# audio.net
KiCad netlist of a schematic drawn in EAGLE
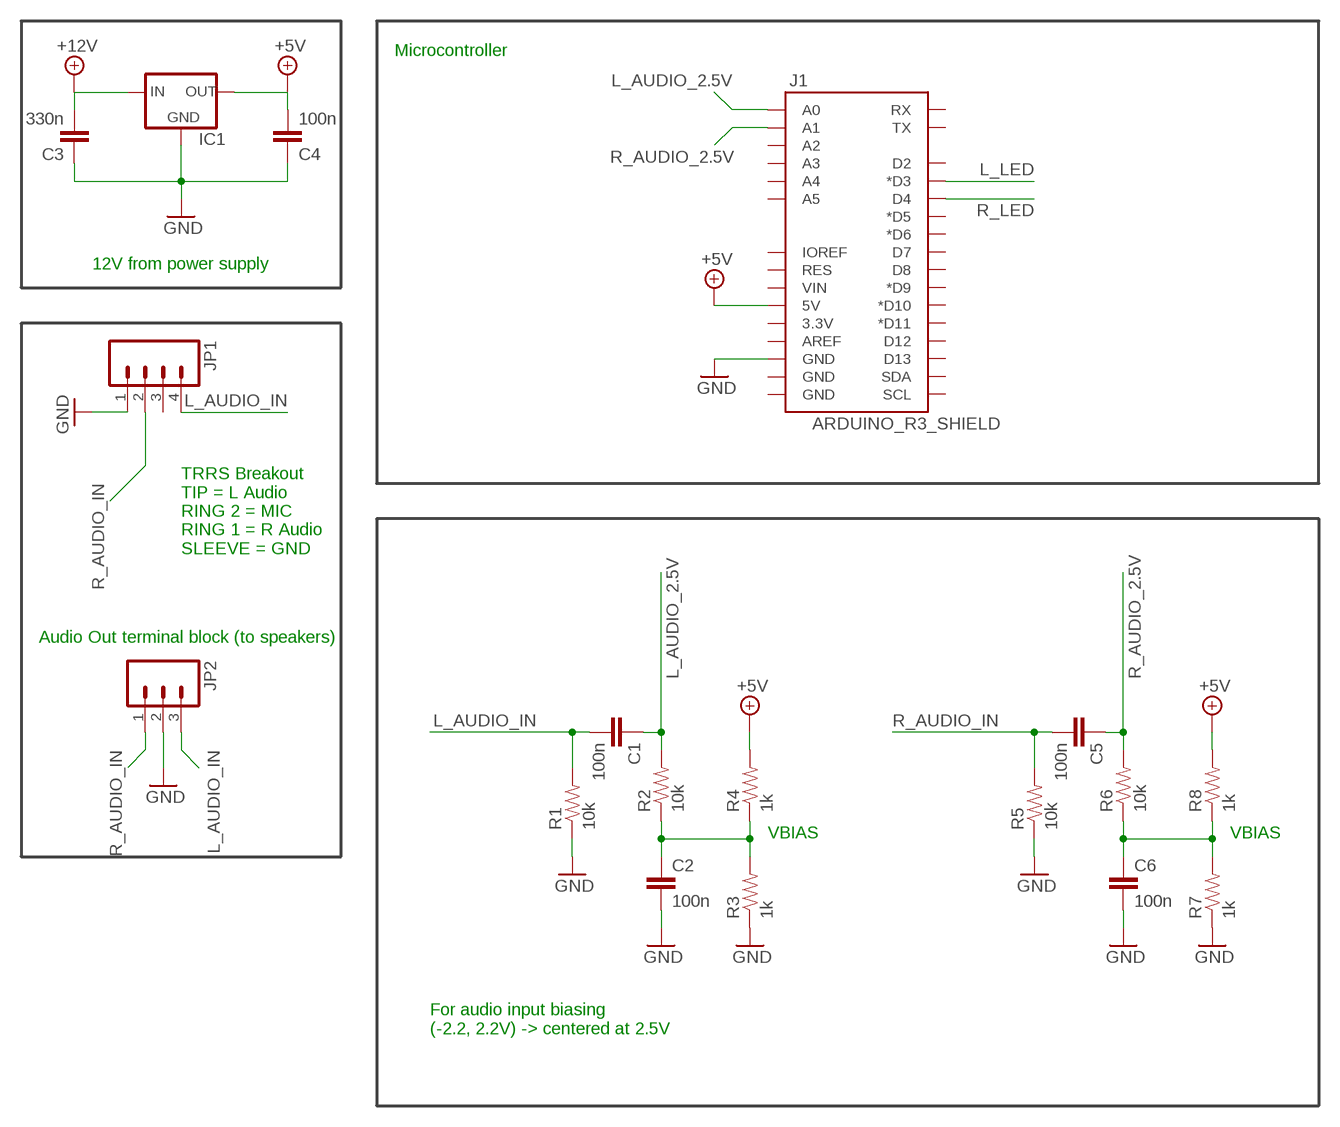
[diagram p0: schematic, sheet 1]

(export (version "E")
  (design (tool "Eeschema 10.0.6"))
  (components
    (comp (ref "C1")
      (value "100n")
      (footprint "eagle-import:AXIAL-5MM")
      (libsource (lib "eagle-import") (part "CAP_"))
    )
    (comp (ref "C2")
      (value "100n")
      (footprint "eagle-import:AXIAL-5MM")
      (libsource (lib "eagle-import") (part "CAP_"))
    )
    (comp (ref "C3")
      (value "330n")
      (footprint "eagle-import:AXIAL-5MM")
      (libsource (lib "eagle-import") (part "CAP_"))
    )
    (comp (ref "C4")
      (value "100n")
      (footprint "eagle-import:AXIAL-5MM")
      (libsource (lib "eagle-import") (part "CAP_"))
    )
    (comp (ref "C5")
      (value "100n")
      (footprint "eagle-import:AXIAL-5MM")
      (libsource (lib "eagle-import") (part "CAP_"))
    )
    (comp (ref "C6")
      (value "100n")
      (footprint "eagle-import:AXIAL-5MM")
      (libsource (lib "eagle-import") (part "CAP_"))
    )
    (comp (ref "IC1")
      (value "5VREG_L7805SPACED")
      (footprint "eagle-import:TO-220-SPACED")
      (libsource (lib "eagle-import") (part "5VREG_L7805SPACED"))
    )
    (comp (ref "J1")
      (value "ARDUINO_R3_SHIELD")
      (footprint "eagle-import:UNO_R3_SHIELD")
      (libsource (lib "eagle-import") (part "ARDUINO_R3_SHIELD"))
    )
    (comp (ref "JP1")
      (value "M04")
      (footprint "eagle-import:1X04")
      (libsource (lib "eagle-import") (part "M04"))
    )
    (comp (ref "JP2")
      (value "M03")
      (footprint "eagle-import:1X03")
      (libsource (lib "eagle-import") (part "M03"))
    )
    (comp (ref "R1")
      (value "10k")
      (footprint "eagle-import:AXIAL-0.4")
      (libsource (lib "eagle-import") (part "RESISTORPTH-1/4W"))
    )
    (comp (ref "R2")
      (value "10k")
      (footprint "eagle-import:AXIAL-0.4")
      (libsource (lib "eagle-import") (part "RESISTORPTH-1/4W"))
    )
    (comp (ref "R3")
      (value "1k")
      (footprint "eagle-import:AXIAL-0.4")
      (libsource (lib "eagle-import") (part "RESISTORPTH-1/4W"))
    )
    (comp (ref "R4")
      (value "1k")
      (footprint "eagle-import:AXIAL-0.4")
      (libsource (lib "eagle-import") (part "RESISTORPTH-1/4W"))
    )
    (comp (ref "R5")
      (value "10k")
      (footprint "eagle-import:AXIAL-0.4")
      (libsource (lib "eagle-import") (part "RESISTORPTH-1/4W"))
    )
    (comp (ref "R6")
      (value "10k")
      (footprint "eagle-import:AXIAL-0.4")
      (libsource (lib "eagle-import") (part "RESISTORPTH-1/4W"))
    )
    (comp (ref "R7")
      (value "1k")
      (footprint "eagle-import:AXIAL-0.4")
      (libsource (lib "eagle-import") (part "RESISTORPTH-1/4W"))
    )
    (comp (ref "R8")
      (value "1k")
      (footprint "eagle-import:AXIAL-0.4")
      (libsource (lib "eagle-import") (part "RESISTORPTH-1/4W"))
    )
  )
  (nets
    (net (code "1") (name "+5V") (class "Default")
      (node (ref "C4") (pin "P$2") (pinfunction "2_P$2") (pintype "passive"))
      (node (ref "IC1") (pin "3") (pinfunction "OUT_3") (pintype "output"))
      (node (ref "J1") (pin "5V") (pinfunction "5V_5V") (pintype "bidirectional"))
      (node (ref "R4") (pin "P$2") (pinfunction "2_P$2") (pintype "passive"))
      (node (ref "R8") (pin "P$2") (pinfunction "2_P$2") (pintype "passive"))
    )
    (net (code "2") (name "+12V") (class "Default")
      (node (ref "C3") (pin "P$2") (pinfunction "2_P$2") (pintype "passive"))
      (node (ref "IC1") (pin "1") (pinfunction "IN_1") (pintype "input"))
    )
    (net (code "3") (name "/L_AUDIO_2.5V") (class "Default")
      (node (ref "C1") (pin "P$1") (pinfunction "1_P$1") (pintype "passive"))
      (node (ref "J1") (pin "A0") (pinfunction "A0_A0") (pintype "bidirectional"))
      (node (ref "R2") (pin "P$2") (pinfunction "2_P$2") (pintype "passive"))
    )
    (net (code "4") (name "/L_AUDIO_IN") (class "Default")
      (node (ref "C1") (pin "P$2") (pinfunction "2_P$2") (pintype "passive"))
      (node (ref "JP1") (pin "4") (pinfunction "4_4") (pintype "passive"))
      (node (ref "JP2") (pin "3") (pinfunction "3_3") (pintype "passive"))
      (node (ref "R1") (pin "P$2") (pinfunction "2_P$2") (pintype "passive"))
    )
    (net (code "5") (name "/L_LED") (class "Default")
      (node (ref "J1") (pin "D3") (pinfunction "*D3_D3") (pintype "bidirectional"))
    )
    (net (code "6") (name "/R_AUDIO_2.5V") (class "Default")
      (node (ref "C5") (pin "P$1") (pinfunction "1_P$1") (pintype "passive"))
      (node (ref "J1") (pin "A1") (pinfunction "A1_A1") (pintype "bidirectional"))
      (node (ref "R6") (pin "P$2") (pinfunction "2_P$2") (pintype "passive"))
    )
    (net (code "7") (name "/R_AUDIO_IN") (class "Default")
      (node (ref "C5") (pin "P$2") (pinfunction "2_P$2") (pintype "passive"))
      (node (ref "JP1") (pin "2") (pinfunction "2_2") (pintype "passive"))
      (node (ref "JP2") (pin "1") (pinfunction "1_1") (pintype "passive"))
      (node (ref "R5") (pin "P$2") (pinfunction "2_P$2") (pintype "passive"))
    )
    (net (code "8") (name "/R_LED") (class "Default")
      (node (ref "J1") (pin "D4") (pinfunction "D4_D4") (pintype "bidirectional"))
    )
    (net (code "9") (name "GND") (class "Default")
      (node (ref "C2") (pin "P$2") (pinfunction "2_P$2") (pintype "passive"))
      (node (ref "C3") (pin "P$1") (pinfunction "1_P$1") (pintype "passive"))
      (node (ref "C4") (pin "P$1") (pinfunction "1_P$1") (pintype "passive"))
      (node (ref "C6") (pin "P$2") (pinfunction "2_P$2") (pintype "passive"))
      (node (ref "IC1") (pin "2") (pinfunction "GND_2") (pintype "input"))
      (node (ref "J1") (pin "GND@2") (pinfunction "GND_GND@2") (pintype "bidirectional"))
      (node (ref "JP1") (pin "1") (pinfunction "1_1") (pintype "passive"))
      (node (ref "JP2") (pin "2") (pinfunction "2_2") (pintype "passive"))
      (node (ref "R1") (pin "P$1") (pinfunction "1_P$1") (pintype "passive"))
      (node (ref "R3") (pin "P$1") (pinfunction "1_P$1") (pintype "passive"))
      (node (ref "R5") (pin "P$1") (pinfunction "1_P$1") (pintype "passive"))
      (node (ref "R7") (pin "P$1") (pinfunction "1_P$1") (pintype "passive"))
    )
    (net (code "10") (name "Net-(C2-1)") (class "Default")
      (node (ref "C2") (pin "P$1") (pinfunction "1_P$1") (pintype "passive"))
      (node (ref "R2") (pin "P$1") (pinfunction "1_P$1") (pintype "passive"))
      (node (ref "R3") (pin "P$2") (pinfunction "2_P$2") (pintype "passive"))
      (node (ref "R4") (pin "P$1") (pinfunction "1_P$1") (pintype "passive"))
    )
    (net (code "11") (name "Net-(C6-1)") (class "Default")
      (node (ref "C6") (pin "P$1") (pinfunction "1_P$1") (pintype "passive"))
      (node (ref "R6") (pin "P$1") (pinfunction "1_P$1") (pintype "passive"))
      (node (ref "R7") (pin "P$2") (pinfunction "2_P$2") (pintype "passive"))
      (node (ref "R8") (pin "P$1") (pinfunction "1_P$1") (pintype "passive"))
    )
    (net (code "12") (name "unconnected-(J1-*D5-PadD5)") (class "Default")
      (node (ref "J1") (pin "D5") (pinfunction "*D5_D5") (pintype "bidirectional"))
    )
    (net (code "13") (name "unconnected-(J1-*D6-PadD6)") (class "Default")
      (node (ref "J1") (pin "D6") (pinfunction "*D6_D6") (pintype "bidirectional"))
    )
    (net (code "14") (name "unconnected-(J1-*D9-PadD9)") (class "Default")
      (node (ref "J1") (pin "D9") (pinfunction "*D9_D9") (pintype "bidirectional"))
    )
    (net (code "15") (name "unconnected-(J1-*D10-PadD10)") (class "Default")
      (node (ref "J1") (pin "D10") (pinfunction "*D10_D10") (pintype "bidirectional"))
    )
    (net (code "16") (name "unconnected-(J1-*D11-PadD11)") (class "Default")
      (node (ref "J1") (pin "D11") (pinfunction "*D11_D11") (pintype "bidirectional"))
    )
    (net (code "17") (name "unconnected-(J1-GND-PadGND@0)") (class "Default")
      (node (ref "J1") (pin "GND@0") (pinfunction "GND_GND@0") (pintype "bidirectional"))
    )
    (net (code "18") (name "unconnected-(J1-GND-PadGND@1)") (class "Default")
      (node (ref "J1") (pin "GND@1") (pinfunction "GND_GND@1") (pintype "bidirectional"))
    )
    (net (code "19") (name "unconnected-(J1-Pad3.3V)") (class "Default")
      (node (ref "J1") (pin "3.3V") (pinfunction "3.3V_3.3V") (pintype "bidirectional"))
    )
    (net (code "20") (name "unconnected-(J1-PadA2)") (class "Default")
      (node (ref "J1") (pin "A2") (pinfunction "A2_A2") (pintype "bidirectional"))
    )
    (net (code "21") (name "unconnected-(J1-PadA3)") (class "Default")
      (node (ref "J1") (pin "A3") (pinfunction "A3_A3") (pintype "bidirectional"))
    )
    (net (code "22") (name "unconnected-(J1-PadA4)") (class "Default")
      (node (ref "J1") (pin "A4") (pinfunction "A4_A4") (pintype "bidirectional"))
    )
    (net (code "23") (name "unconnected-(J1-PadA5)") (class "Default")
      (node (ref "J1") (pin "A5") (pinfunction "A5_A5") (pintype "bidirectional"))
    )
    (net (code "24") (name "unconnected-(J1-PadAREF)") (class "Default")
      (node (ref "J1") (pin "AREF") (pinfunction "AREF_AREF") (pintype "bidirectional"))
    )
    (net (code "25") (name "unconnected-(J1-PadD2)") (class "Default")
      (node (ref "J1") (pin "D2") (pinfunction "D2_D2") (pintype "bidirectional"))
    )
    (net (code "26") (name "unconnected-(J1-PadD7)") (class "Default")
      (node (ref "J1") (pin "D7") (pinfunction "D7_D7") (pintype "bidirectional"))
    )
    (net (code "27") (name "unconnected-(J1-PadD8)") (class "Default")
      (node (ref "J1") (pin "D8") (pinfunction "D8_D8") (pintype "bidirectional"))
    )
    (net (code "28") (name "unconnected-(J1-PadD12)") (class "Default")
      (node (ref "J1") (pin "D12") (pinfunction "D12_D12") (pintype "bidirectional"))
    )
    (net (code "29") (name "unconnected-(J1-PadD13)") (class "Default")
      (node (ref "J1") (pin "D13") (pinfunction "D13_D13") (pintype "bidirectional"))
    )
    (net (code "30") (name "unconnected-(J1-PadIOREF)") (class "Default")
      (node (ref "J1") (pin "IOREF") (pinfunction "IOREF_IOREF") (pintype "bidirectional"))
    )
    (net (code "31") (name "unconnected-(J1-PadRES)") (class "Default")
      (node (ref "J1") (pin "RES") (pinfunction "RES_RES") (pintype "bidirectional"))
    )
    (net (code "32") (name "unconnected-(J1-PadRX)") (class "Default")
      (node (ref "J1") (pin "RX") (pinfunction "RX_RX") (pintype "bidirectional"))
    )
    (net (code "33") (name "unconnected-(J1-PadSCL)") (class "Default")
      (node (ref "J1") (pin "SCL") (pinfunction "SCL_SCL") (pintype "bidirectional"))
    )
    (net (code "34") (name "unconnected-(J1-PadSDA)") (class "Default")
      (node (ref "J1") (pin "SDA") (pinfunction "SDA_SDA") (pintype "bidirectional"))
    )
    (net (code "35") (name "unconnected-(J1-PadTX)") (class "Default")
      (node (ref "J1") (pin "TX") (pinfunction "TX_TX") (pintype "bidirectional"))
    )
    (net (code "36") (name "unconnected-(J1-PadVIN)") (class "Default")
      (node (ref "J1") (pin "VIN") (pinfunction "VIN_VIN") (pintype "bidirectional"))
    )
    (net (code "37") (name "unconnected-(JP1-Pad3)") (class "Default")
      (node (ref "JP1") (pin "3") (pinfunction "3_3") (pintype "passive"))
    )
  )
)
